# smart_watch-BASIC-TOP.net
KiCad netlist of a schematic drawn in EAGLE
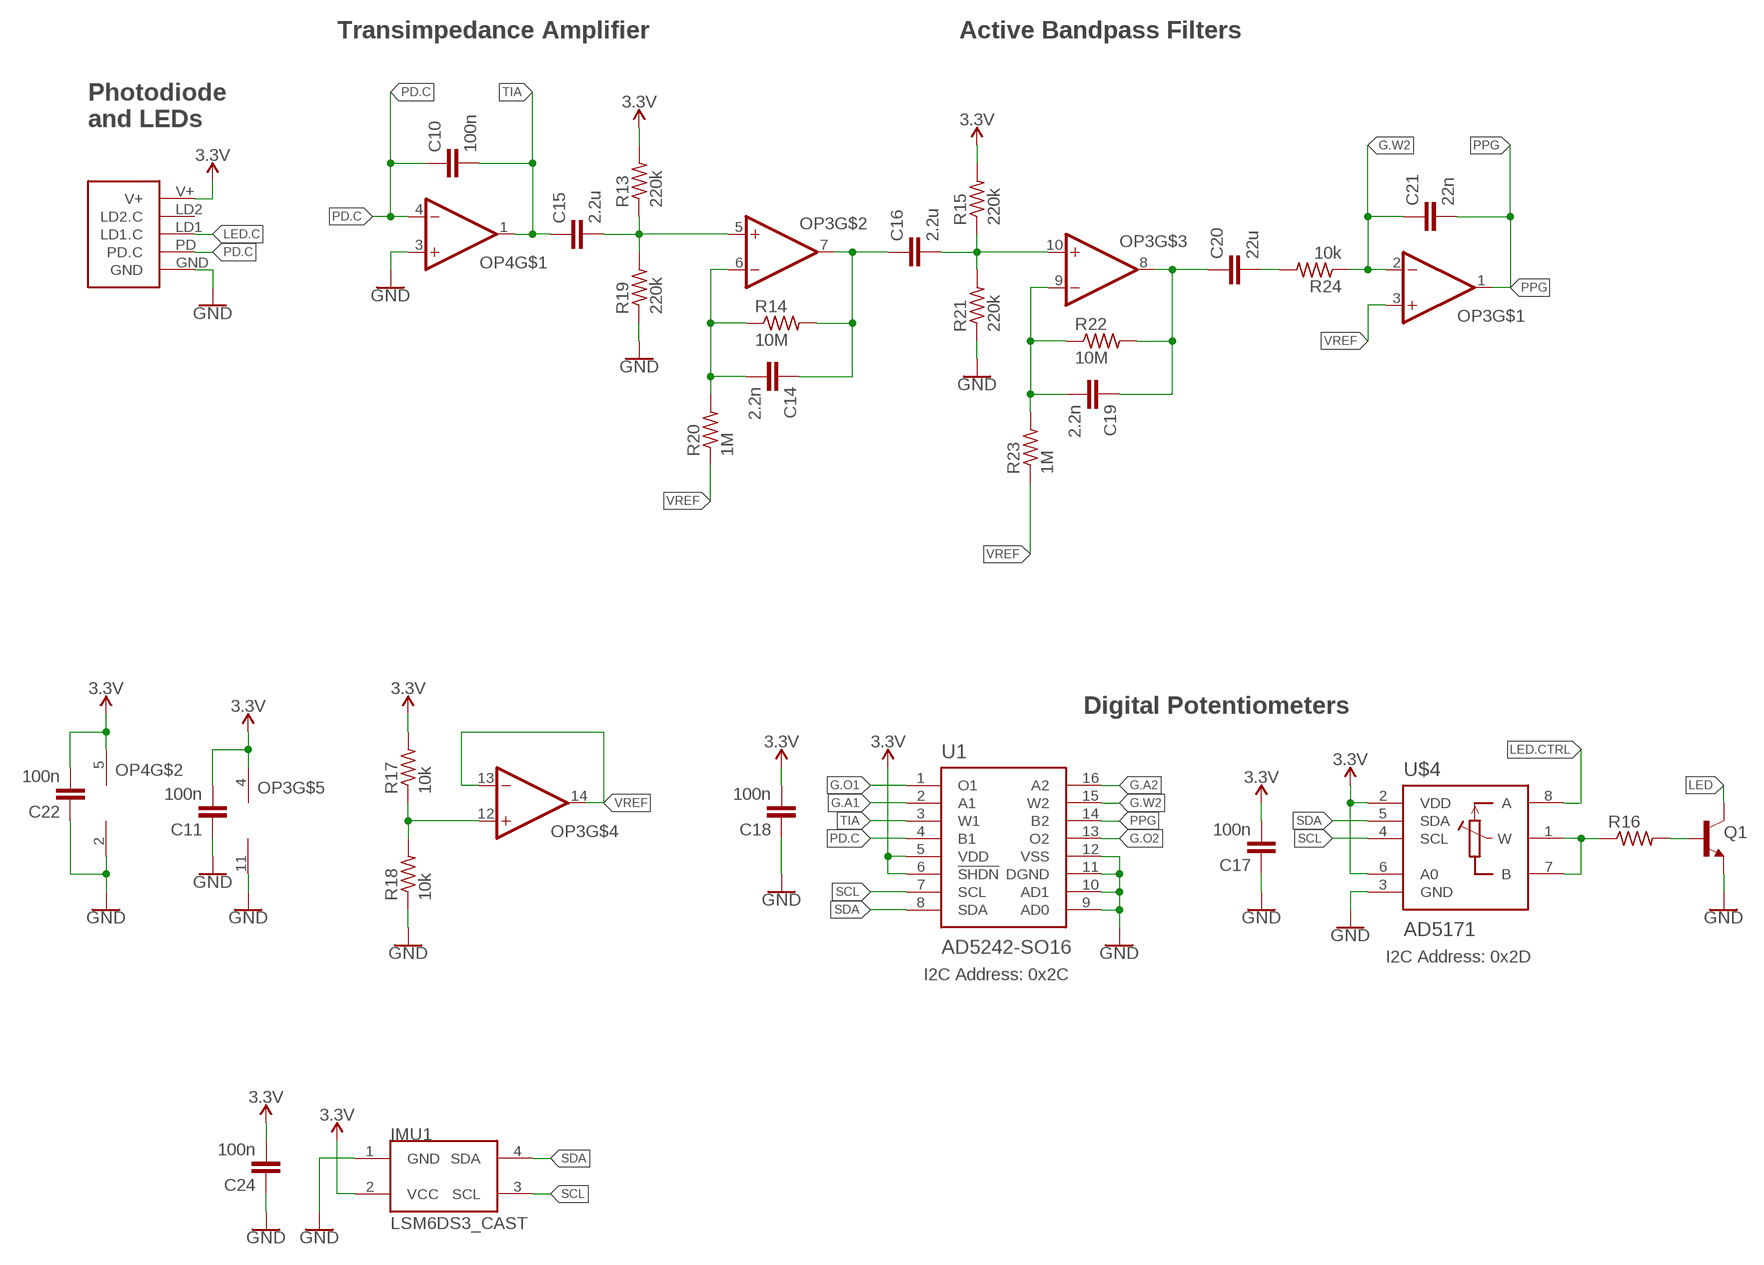
[diagram p0: schematic, sheet 1]

(export (version "E")
  (design (tool "Eeschema 10.0.6"))
  (components
    (comp (ref "C10")
      (value "100n")
      (footprint "eagle-import:C0603")
      (libsource (lib "eagle-import") (part "CAPACITOR0603"))
    )
    (comp (ref "C11")
      (value "100n")
      (footprint "eagle-import:C0603")
      (libsource (lib "eagle-import") (part "CAPACITOR0603"))
    )
    (comp (ref "C14")
      (value "2.2n")
      (footprint "eagle-import:C0603")
      (libsource (lib "eagle-import") (part "CAPACITOR0603"))
    )
    (comp (ref "C15")
      (value "2.2u")
      (footprint "eagle-import:C0603")
      (libsource (lib "eagle-import") (part "CAPACITOR0603"))
    )
    (comp (ref "C16")
      (value "2.2u")
      (footprint "eagle-import:C0603")
      (libsource (lib "eagle-import") (part "CAPACITOR0603"))
    )
    (comp (ref "C17")
      (value "100n")
      (footprint "eagle-import:C0603")
      (libsource (lib "eagle-import") (part "CAPACITOR0603"))
    )
    (comp (ref "C18")
      (value "100n")
      (footprint "eagle-import:C0603")
      (libsource (lib "eagle-import") (part "CAPACITOR0603"))
    )
    (comp (ref "C19")
      (value "2.2n")
      (footprint "eagle-import:C0603")
      (libsource (lib "eagle-import") (part "CAPACITOR0603"))
    )
    (comp (ref "C20")
      (value "22u")
      (footprint "eagle-import:C0603")
      (libsource (lib "eagle-import") (part "CAPACITOR0603"))
    )
    (comp (ref "C21")
      (value "22n")
      (footprint "eagle-import:C0603")
      (libsource (lib "eagle-import") (part "CAPACITOR0603"))
    )
    (comp (ref "C22")
      (value "100n")
      (footprint "eagle-import:C0603")
      (libsource (lib "eagle-import") (part "CAPACITOR0603"))
    )
    (comp (ref "C24")
      (value "100n")
      (footprint "eagle-import:C0603")
      (libsource (lib "eagle-import") (part "CAPACITOR0603"))
    )
    (comp (ref "IMU1")
      (value "LSM6DS3_CAST")
      (footprint "eagle-import:LSM6DS3_CAST")
      (libsource (lib "eagle-import") (part "LSM6DS3_CAST"))
    )
    (comp (ref "OP3")
      (value "OP-QUAD-SO14")
      (footprint "eagle-import:SO14")
      (libsource (lib "eagle-import") (part "OP-QUAD-SO14"))
    )
    (comp (ref "OP4")
      (value "OP-SINGLEOT")
      (footprint "eagle-import:SOT23-5")
      (libsource (lib "eagle-import") (part "OP-SINGLEOT"))
    )
    (comp (ref "Q1")
      (value "NPN-GENERIC")
      (footprint "eagle-import:SOT23-3")
      (libsource (lib "eagle-import") (part "NPN-GENERIC"))
    )
    (comp (ref "R13")
      (value "220k")
      (footprint "eagle-import:R0603")
      (libsource (lib "eagle-import") (part "RESISTOR0603"))
    )
    (comp (ref "R14")
      (value "10M")
      (footprint "eagle-import:R0603")
      (libsource (lib "eagle-import") (part "RESISTOR0603"))
    )
    (comp (ref "R15")
      (value "220k")
      (footprint "eagle-import:R0603")
      (libsource (lib "eagle-import") (part "RESISTOR0603"))
    )
    (comp (ref "R16")
      (value "RESISTOR0603")
      (footprint "eagle-import:R0603")
      (libsource (lib "eagle-import") (part "RESISTOR0603"))
    )
    (comp (ref "R17")
      (value "10k")
      (footprint "eagle-import:R0402")
      (libsource (lib "eagle-import") (part "RESISTOR0402"))
    )
    (comp (ref "R18")
      (value "10k")
      (footprint "eagle-import:R0402")
      (libsource (lib "eagle-import") (part "RESISTOR0402"))
    )
    (comp (ref "R19")
      (value "220k")
      (footprint "eagle-import:R0603")
      (libsource (lib "eagle-import") (part "RESISTOR0603"))
    )
    (comp (ref "R20")
      (value "1M")
      (footprint "eagle-import:R0603")
      (libsource (lib "eagle-import") (part "RESISTOR0603"))
    )
    (comp (ref "R21")
      (value "220k")
      (footprint "eagle-import:R0603")
      (libsource (lib "eagle-import") (part "RESISTOR0603"))
    )
    (comp (ref "R22")
      (value "10M")
      (footprint "eagle-import:R0603")
      (libsource (lib "eagle-import") (part "RESISTOR0603"))
    )
    (comp (ref "R23")
      (value "1M")
      (footprint "eagle-import:R0603")
      (libsource (lib "eagle-import") (part "RESISTOR0603"))
    )
    (comp (ref "R24")
      (value "10k")
      (footprint "eagle-import:R0603")
      (libsource (lib "eagle-import") (part "RESISTOR0603"))
    )
    (comp (ref "U$3")
      (value "PPG.MODULE.2")
      (footprint "eagle-import:PPG.MODULE.2")
      (libsource (lib "eagle-import") (part "PPG.MODULE.2"))
    )
    (comp (ref "U$4")
      (value "AD5171")
      (footprint "eagle-import:SOT-23-8")
      (libsource (lib "eagle-import") (part "AD5171"))
    )
    (comp (ref "U1")
      (value "AD5242-SO16")
      (footprint "eagle-import:SO16")
      (libsource (lib "eagle-import") (part "AD5242-SO16"))
    )
  )
  (nets
    (net (code "1") (name "3.3V") (class "Default")
      (node (ref "C11") (pin "2") (pinfunction "2_2") (pintype "passive"))
      (node (ref "C17") (pin "2") (pinfunction "2_2") (pintype "passive"))
      (node (ref "C18") (pin "2") (pinfunction "2_2") (pintype "passive"))
      (node (ref "C22") (pin "2") (pinfunction "2_2") (pintype "passive"))
      (node (ref "C24") (pin "2") (pinfunction "2_2") (pintype "passive"))
      (node (ref "IMU1") (pin "2") (pinfunction "VCC_2") (pintype "bidirectional"))
      (node (ref "OP3") (pin "4") (pinfunction "V+_4") (pintype "power_in"))
      (node (ref "OP4") (pin "5") (pinfunction "V+_5") (pintype "power_in"))
      (node (ref "R13") (pin "2") (pinfunction "2_2") (pintype "passive"))
      (node (ref "R15") (pin "2") (pinfunction "2_2") (pintype "passive"))
      (node (ref "R17") (pin "2") (pinfunction "2_2") (pintype "passive"))
      (node (ref "U$3") (pin "V+") (pinfunction "V+_V+") (pintype "bidirectional"))
      (node (ref "U$4") (pin "2") (pinfunction "VDD_2") (pintype "bidirectional"))
      (node (ref "U$4") (pin "6") (pinfunction "A0_6") (pintype "bidirectional"))
      (node (ref "U1") (pin "5") (pinfunction "VDD_5") (pintype "bidirectional"))
      (node (ref "U1") (pin "6") (pinfunction "~{SHDN}_6") (pintype "bidirectional"))
    )
    (net (code "2") (name "G.A1") (class "Default")
      (node (ref "U1") (pin "2") (pinfunction "A1_2") (pintype "bidirectional"))
    )
    (net (code "3") (name "G.A2") (class "Default")
      (node (ref "U1") (pin "16") (pinfunction "A2_16") (pintype "bidirectional"))
    )
    (net (code "4") (name "G.O1") (class "Default")
      (node (ref "U1") (pin "1") (pinfunction "O1_1") (pintype "bidirectional"))
    )
    (net (code "5") (name "G.O2") (class "Default")
      (node (ref "U1") (pin "13") (pinfunction "O2_13") (pintype "bidirectional"))
    )
    (net (code "6") (name "G.W2") (class "Default")
      (node (ref "C21") (pin "1") (pinfunction "1_1") (pintype "passive"))
      (node (ref "OP3") (pin "2") (pinfunction "-IN_2") (pintype "input"))
      (node (ref "R24") (pin "1") (pinfunction "1_1") (pintype "passive"))
      (node (ref "U1") (pin "15") (pinfunction "W2_15") (pintype "bidirectional"))
    )
    (net (code "7") (name "GND") (class "Default")
      (node (ref "C11") (pin "1") (pinfunction "1_1") (pintype "passive"))
      (node (ref "C17") (pin "1") (pinfunction "1_1") (pintype "passive"))
      (node (ref "C18") (pin "1") (pinfunction "1_1") (pintype "passive"))
      (node (ref "C22") (pin "1") (pinfunction "1_1") (pintype "passive"))
      (node (ref "C24") (pin "1") (pinfunction "1_1") (pintype "passive"))
      (node (ref "IMU1") (pin "1") (pinfunction "GND_1") (pintype "bidirectional"))
      (node (ref "OP3") (pin "11") (pinfunction "V-_11") (pintype "power_in"))
      (node (ref "OP4") (pin "2") (pinfunction "V-_2") (pintype "power_in"))
      (node (ref "OP4") (pin "3") (pinfunction "+IN_3") (pintype "input"))
      (node (ref "Q1") (pin "2") (pinfunction "E_2") (pintype "passive"))
      (node (ref "R18") (pin "1") (pinfunction "1_1") (pintype "passive"))
      (node (ref "R19") (pin "1") (pinfunction "1_1") (pintype "passive"))
      (node (ref "R21") (pin "1") (pinfunction "1_1") (pintype "passive"))
      (node (ref "U$3") (pin "GND") (pinfunction "GND_GND") (pintype "bidirectional"))
      (node (ref "U$4") (pin "3") (pinfunction "GND_3") (pintype "bidirectional"))
      (node (ref "U1") (pin "10") (pinfunction "AD1_10") (pintype "bidirectional"))
      (node (ref "U1") (pin "11") (pinfunction "DGND_11") (pintype "bidirectional"))
      (node (ref "U1") (pin "12") (pinfunction "VSS_12") (pintype "bidirectional"))
      (node (ref "U1") (pin "9") (pinfunction "AD0_9") (pintype "bidirectional"))
    )
    (net (code "8") (name "LED") (class "Default")
      (node (ref "Q1") (pin "3") (pinfunction "C_3") (pintype "passive"))
    )
    (net (code "9") (name "LED.C") (class "Default")
      (node (ref "U$3") (pin "LD1") (pinfunction "LD1.C_LD1") (pintype "bidirectional"))
    )
    (net (code "10") (name "LED.CTRL") (class "Default")
      (node (ref "U$4") (pin "8") (pinfunction "A_8") (pintype "bidirectional"))
    )
    (net (code "11") (name "Net-(C20-Pad2)") (class "Default")
      (node (ref "C20") (pin "2") (pinfunction "2_2") (pintype "passive"))
      (node (ref "R24") (pin "2") (pinfunction "2_2") (pintype "passive"))
    )
    (net (code "12") (name "Net-(OP3B-+IN)") (class "Default")
      (node (ref "C15") (pin "2") (pinfunction "2_2") (pintype "passive"))
      (node (ref "OP3") (pin "5") (pinfunction "+IN_5") (pintype "input"))
      (node (ref "R13") (pin "1") (pinfunction "1_1") (pintype "passive"))
      (node (ref "R19") (pin "2") (pinfunction "2_2") (pintype "passive"))
    )
    (net (code "13") (name "Net-(OP3B--IN)") (class "Default")
      (node (ref "C14") (pin "2") (pinfunction "2_2") (pintype "passive"))
      (node (ref "OP3") (pin "6") (pinfunction "-IN_6") (pintype "input"))
      (node (ref "R14") (pin "1") (pinfunction "1_1") (pintype "passive"))
      (node (ref "R20") (pin "2") (pinfunction "2_2") (pintype "passive"))
    )
    (net (code "14") (name "Net-(OP3B-OUT)") (class "Default")
      (node (ref "C14") (pin "1") (pinfunction "1_1") (pintype "passive"))
      (node (ref "C16") (pin "1") (pinfunction "1_1") (pintype "passive"))
      (node (ref "OP3") (pin "7") (pinfunction "OUT_7") (pintype "output"))
      (node (ref "R14") (pin "2") (pinfunction "2_2") (pintype "passive"))
    )
    (net (code "15") (name "Net-(OP3C-+IN)") (class "Default")
      (node (ref "C16") (pin "2") (pinfunction "2_2") (pintype "passive"))
      (node (ref "OP3") (pin "10") (pinfunction "+IN_10") (pintype "input"))
      (node (ref "R15") (pin "1") (pinfunction "1_1") (pintype "passive"))
      (node (ref "R21") (pin "2") (pinfunction "2_2") (pintype "passive"))
    )
    (net (code "16") (name "Net-(OP3C--IN)") (class "Default")
      (node (ref "C19") (pin "2") (pinfunction "2_2") (pintype "passive"))
      (node (ref "OP3") (pin "9") (pinfunction "-IN_9") (pintype "input"))
      (node (ref "R22") (pin "1") (pinfunction "1_1") (pintype "passive"))
      (node (ref "R23") (pin "2") (pinfunction "2_2") (pintype "passive"))
    )
    (net (code "17") (name "Net-(OP3C-OUT)") (class "Default")
      (node (ref "C19") (pin "1") (pinfunction "1_1") (pintype "passive"))
      (node (ref "C20") (pin "1") (pinfunction "1_1") (pintype "passive"))
      (node (ref "OP3") (pin "8") (pinfunction "OUT_8") (pintype "output"))
      (node (ref "R22") (pin "2") (pinfunction "2_2") (pintype "passive"))
    )
    (net (code "18") (name "Net-(OP3D-+IN)") (class "Default")
      (node (ref "OP3") (pin "12") (pinfunction "+IN_12") (pintype "input"))
      (node (ref "R17") (pin "1") (pinfunction "1_1") (pintype "passive"))
      (node (ref "R18") (pin "2") (pinfunction "2_2") (pintype "passive"))
    )
    (net (code "19") (name "Net-(Q1-B)") (class "Default")
      (node (ref "Q1") (pin "1") (pinfunction "B_1") (pintype "passive"))
      (node (ref "R16") (pin "2") (pinfunction "2_2") (pintype "passive"))
    )
    (net (code "20") (name "Net-(U$4-B)") (class "Default")
      (node (ref "R16") (pin "1") (pinfunction "1_1") (pintype "passive"))
      (node (ref "U$4") (pin "1") (pinfunction "W_1") (pintype "bidirectional"))
      (node (ref "U$4") (pin "7") (pinfunction "B_7") (pintype "bidirectional"))
    )
    (net (code "21") (name "PD.C") (class "Default")
      (node (ref "C10") (pin "1") (pinfunction "1_1") (pintype "passive"))
      (node (ref "OP4") (pin "4") (pinfunction "-IN_4") (pintype "input"))
      (node (ref "U$3") (pin "PD") (pinfunction "PD.C_PD") (pintype "bidirectional"))
      (node (ref "U1") (pin "4") (pinfunction "B1_4") (pintype "bidirectional"))
    )
    (net (code "22") (name "PPG") (class "Default")
      (node (ref "C21") (pin "2") (pinfunction "2_2") (pintype "passive"))
      (node (ref "OP3") (pin "1") (pinfunction "OUT_1") (pintype "output"))
      (node (ref "U1") (pin "14") (pinfunction "B2_14") (pintype "bidirectional"))
    )
    (net (code "23") (name "SCL") (class "Default")
      (node (ref "IMU1") (pin "3") (pinfunction "SCL_3") (pintype "bidirectional"))
      (node (ref "U$4") (pin "4") (pinfunction "SCL_4") (pintype "bidirectional"))
      (node (ref "U1") (pin "7") (pinfunction "SCL_7") (pintype "bidirectional"))
    )
    (net (code "24") (name "SDA") (class "Default")
      (node (ref "IMU1") (pin "4") (pinfunction "SDA_4") (pintype "bidirectional"))
      (node (ref "U$4") (pin "5") (pinfunction "SDA_5") (pintype "bidirectional"))
      (node (ref "U1") (pin "8") (pinfunction "SDA_8") (pintype "bidirectional"))
    )
    (net (code "25") (name "TIA") (class "Default")
      (node (ref "C10") (pin "2") (pinfunction "2_2") (pintype "passive"))
      (node (ref "C15") (pin "1") (pinfunction "1_1") (pintype "passive"))
      (node (ref "OP4") (pin "1") (pinfunction "OUT_1") (pintype "output"))
      (node (ref "U1") (pin "3") (pinfunction "W1_3") (pintype "bidirectional"))
    )
    (net (code "26") (name "VREF") (class "Default")
      (node (ref "OP3") (pin "13") (pinfunction "-IN_13") (pintype "input"))
      (node (ref "OP3") (pin "14") (pinfunction "OUT_14") (pintype "output"))
      (node (ref "OP3") (pin "3") (pinfunction "+IN_3") (pintype "input"))
      (node (ref "R20") (pin "1") (pinfunction "1_1") (pintype "passive"))
      (node (ref "R23") (pin "1") (pinfunction "1_1") (pintype "passive"))
    )
    (net (code "27") (name "unconnected-(U$3-LD2.C-PadLD2)") (class "Default")
      (node (ref "U$3") (pin "LD2") (pinfunction "LD2.C_LD2") (pintype "bidirectional"))
    )
  )
)
